# Controller_Interface.net
KiCad netlist of a schematic drawn in Altium Designer
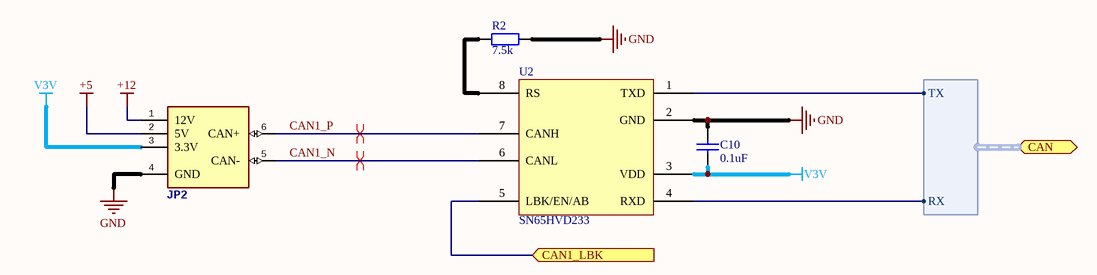
[diagram p0: Controller_Interface.SchDoc]

(export (version "E")
  (design (tool "Eeschema 10.0.6"))
  (components
    (comp (ref "C10")
      (value "0.1uF")
      (footprint "CAPC1608X06N (0603)")
      (description "Capacitor (Semiconductor SIM Model)")
      (fields (field (name "Comment") "Cap Semi") (field (name "PUBLISHER") "Altium Limited"))
      (libsource (lib "miStepper_SchematicLib") (part "Cap Semi"))
    )
    (comp (ref "JP2")
      (value "JST PH Series, 2mm Pitch 6 Way 1 Row Right Angle PCB Header, Solder Termination, 2A   Source:  Datasheet")
      (footprint "S6B-PH-SM4-TB(LF)(SN)")
      (description "Custom header for miStepper")
      (fields
        (field (name "FARNELL_PART_NUMBER") "9492658")
        (field (name "MANUFACTURER_PART_NUMBER") "S6B-PH-SM4-TB(LF)(SN)")
      )
      (libsource (lib "miStepper_SchematicLib") (part "miStepper-Connector"))
    )
    (comp (ref "R2")
      (value "7.5k")
      (footprint "RESC1608X06N (0603)")
      (description "Resistor")
      (fields (field (name "Comment") "Res") (field (name "PUBLISHER") "Altium Limited"))
      (libsource (lib "miStepper_SchematicLib") (part "Res"))
    )
    (comp (ref "U2")
      (value "SN65HVD233")
      (footprint "SOIC127P600X175-8N")
      (description "3.3V CAN Bus Transceiver")
      (fields (field (name "MANUFACTURER") "Texas Instruments"))
      (libsource (lib "miStepper_SchematicLib") (part "SN65HVD23x"))
    )
  )
  (nets
    (net (code "2") (name "+5") (class "Default")
      (node (ref "JP2") (pin "2") (pinfunction "5V_2") (pintype "power_in"))
    )
    (net (code "3") (name "+12") (class "Default")
      (node (ref "JP2") (pin "1") (pinfunction "12V_1") (pintype "power_in"))
    )
    (net (code "4") (name "/CAN1_LBK") (class "Default")
      (node (ref "U2") (pin "5") (pinfunction "LBK/EN/AB_5") (pintype "passive"))
    )
    (net (code "5") (name "/CAN1_N") (class "Default")
      (node (ref "JP2") (pin "5") (pinfunction "CAN-_5") (pintype "bidirectional"))
      (node (ref "U2") (pin "6") (pinfunction "CANL_6") (pintype "passive"))
    )
    (net (code "6") (name "/CAN1_P") (class "Default")
      (node (ref "JP2") (pin "6") (pinfunction "CAN+_6") (pintype "bidirectional"))
      (node (ref "U2") (pin "7") (pinfunction "CANH_7") (pintype "passive"))
    )
    (net (code "7") (name "/RX") (class "Default")
      (node (ref "U2") (pin "4") (pinfunction "RXD_4") (pintype "passive"))
    )
    (net (code "8") (name "/TX") (class "Default")
      (node (ref "U2") (pin "1") (pinfunction "TXD_1") (pintype "passive"))
    )
    (net (code "10") (name "GND") (class "Default")
      (node (ref "C10") (pin "2") (pinfunction "2_2") (pintype "passive"))
      (node (ref "JP2") (pin "4") (pinfunction "GND_4") (pintype "power_in"))
      (node (ref "R2") (pin "2") (pinfunction "2_2") (pintype "passive"))
      (node (ref "U2") (pin "2") (pinfunction "GND_2") (pintype "passive"))
    )
    (net (code "11") (name "Net-(U2-RS)") (class "Default")
      (node (ref "R2") (pin "1") (pinfunction "1_1") (pintype "passive"))
      (node (ref "U2") (pin "8") (pinfunction "RS_8") (pintype "passive"))
    )
    (net (code "12") (name "V3V") (class "Default")
      (node (ref "C10") (pin "1") (pinfunction "1_1") (pintype "passive"))
      (node (ref "JP2") (pin "3") (pinfunction "3.3V_3") (pintype "power_in"))
      (node (ref "U2") (pin "3") (pinfunction "VDD_3") (pintype "passive"))
    )
  )
)
